# ArduSensor-Force.net
KiCad netlist of a schematic drawn in EAGLE
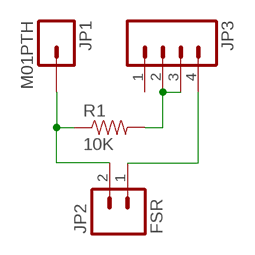
[diagram p0: schematic, sheet 1]

(export (version "E")
  (design (tool "Eeschema 10.0.6"))
  (components
    (comp (ref "JP1")
      (value "M01PTH")
      (footprint "eagle-import:1X01")
      (libsource (lib "eagle-import") (part "M01PTH"))
    )
    (comp (ref "JP2")
      (value "FSR")
      (footprint "eagle-import:1X02")
      (libsource (lib "eagle-import") (part "M02PTH"))
    )
    (comp (ref "JP3")
      (value "M04PTH")
      (footprint "eagle-import:1X04")
      (libsource (lib "eagle-import") (part "M04PTH"))
    )
    (comp (ref "R1")
      (value "10K")
      (footprint "eagle-import:AXIAL-0.3")
      (libsource (lib "eagle-import") (part "RESISTORAXIAL-0.3"))
    )
  )
  (nets
    (net (code "1") (name "Net-(JP2-Pad1)") (class "Default")
      (node (ref "JP2") (pin "1") (pinfunction "1_1") (pintype "passive"))
      (node (ref "JP3") (pin "4") (pinfunction "4_4") (pintype "passive"))
    )
    (net (code "2") (name "Net-(R1-1)") (class "Default")
      (node (ref "JP1") (pin "1") (pinfunction "1_1") (pintype "passive"))
      (node (ref "JP2") (pin "2") (pinfunction "2_2") (pintype "passive"))
      (node (ref "R1") (pin "P$1") (pinfunction "1_P$1") (pintype "passive"))
    )
    (net (code "3") (name "Net-(R1-2)") (class "Default")
      (node (ref "JP3") (pin "2") (pinfunction "2_2") (pintype "passive"))
      (node (ref "JP3") (pin "3") (pinfunction "3_3") (pintype "passive"))
      (node (ref "R1") (pin "P$2") (pinfunction "2_P$2") (pintype "passive"))
    )
    (net (code "4") (name "unconnected-(JP3-Pad1)") (class "Default")
      (node (ref "JP3") (pin "1") (pinfunction "1_1") (pintype "passive"))
    )
  )
)
